# tsop.net
KiCad netlist of a schematic drawn in EAGLE
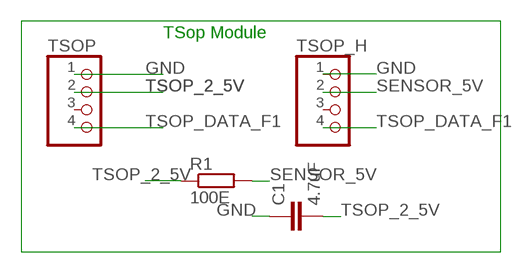
[diagram p0: schematic, sheet 1]

(export (version "E")
  (design (tool "Eeschema 10.0.6"))
  (components
    (comp (ref "C1")
      (value "4.7uF")
      (footprint "eagle-import:C1206")
      (libsource (lib "eagle-import") (part "C-EUC1206"))
    )
    (comp (ref "R1")
      (value "100E")
      (footprint "eagle-import:R1206")
      (libsource (lib "eagle-import") (part "R-EU_R1206"))
    )
    (comp (ref "TSOP")
      (value "PINHD-1X4")
      (footprint "eagle-import:1X04")
      (libsource (lib "eagle-import") (part "PINHD-1X4"))
    )
    (comp (ref "TSOP_H")
      (value "PINHD-1X4")
      (footprint "eagle-import:1X04")
      (libsource (lib "eagle-import") (part "PINHD-1X4"))
    )
  )
  (nets
    (net (code "1") (name "/GND") (class "Default")
      (node (ref "C1") (pin "1") (pinfunction "1_1") (pintype "passive"))
      (node (ref "TSOP") (pin "1") (pinfunction "1_1") (pintype "passive"))
      (node (ref "TSOP_H") (pin "1") (pinfunction "1_1") (pintype "passive"))
    )
    (net (code "2") (name "/SENSOR_5V") (class "Default")
      (node (ref "R1") (pin "2") (pinfunction "2_2") (pintype "passive"))
      (node (ref "TSOP_H") (pin "2") (pinfunction "2_2") (pintype "passive"))
    )
    (net (code "3") (name "/TSOP_2_5V") (class "Default")
      (node (ref "C1") (pin "2") (pinfunction "2_2") (pintype "passive"))
      (node (ref "R1") (pin "1") (pinfunction "1_1") (pintype "passive"))
      (node (ref "TSOP") (pin "2") (pinfunction "2_2") (pintype "passive"))
    )
    (net (code "4") (name "/TSOP_DATA_F1") (class "Default")
      (node (ref "TSOP") (pin "4") (pinfunction "4_4") (pintype "passive"))
      (node (ref "TSOP_H") (pin "4") (pinfunction "4_4") (pintype "passive"))
    )
    (net (code "5") (name "unconnected-(TSOP-Pad3)") (class "Default")
      (node (ref "TSOP") (pin "3") (pinfunction "3_3") (pintype "passive"))
    )
    (net (code "6") (name "unconnected-(TSOP_H-Pad3)") (class "Default")
      (node (ref "TSOP_H") (pin "3") (pinfunction "3_3") (pintype "passive"))
    )
  )
)
